# radio103.net
KiCad netlist of a schematic drawn in EAGLE
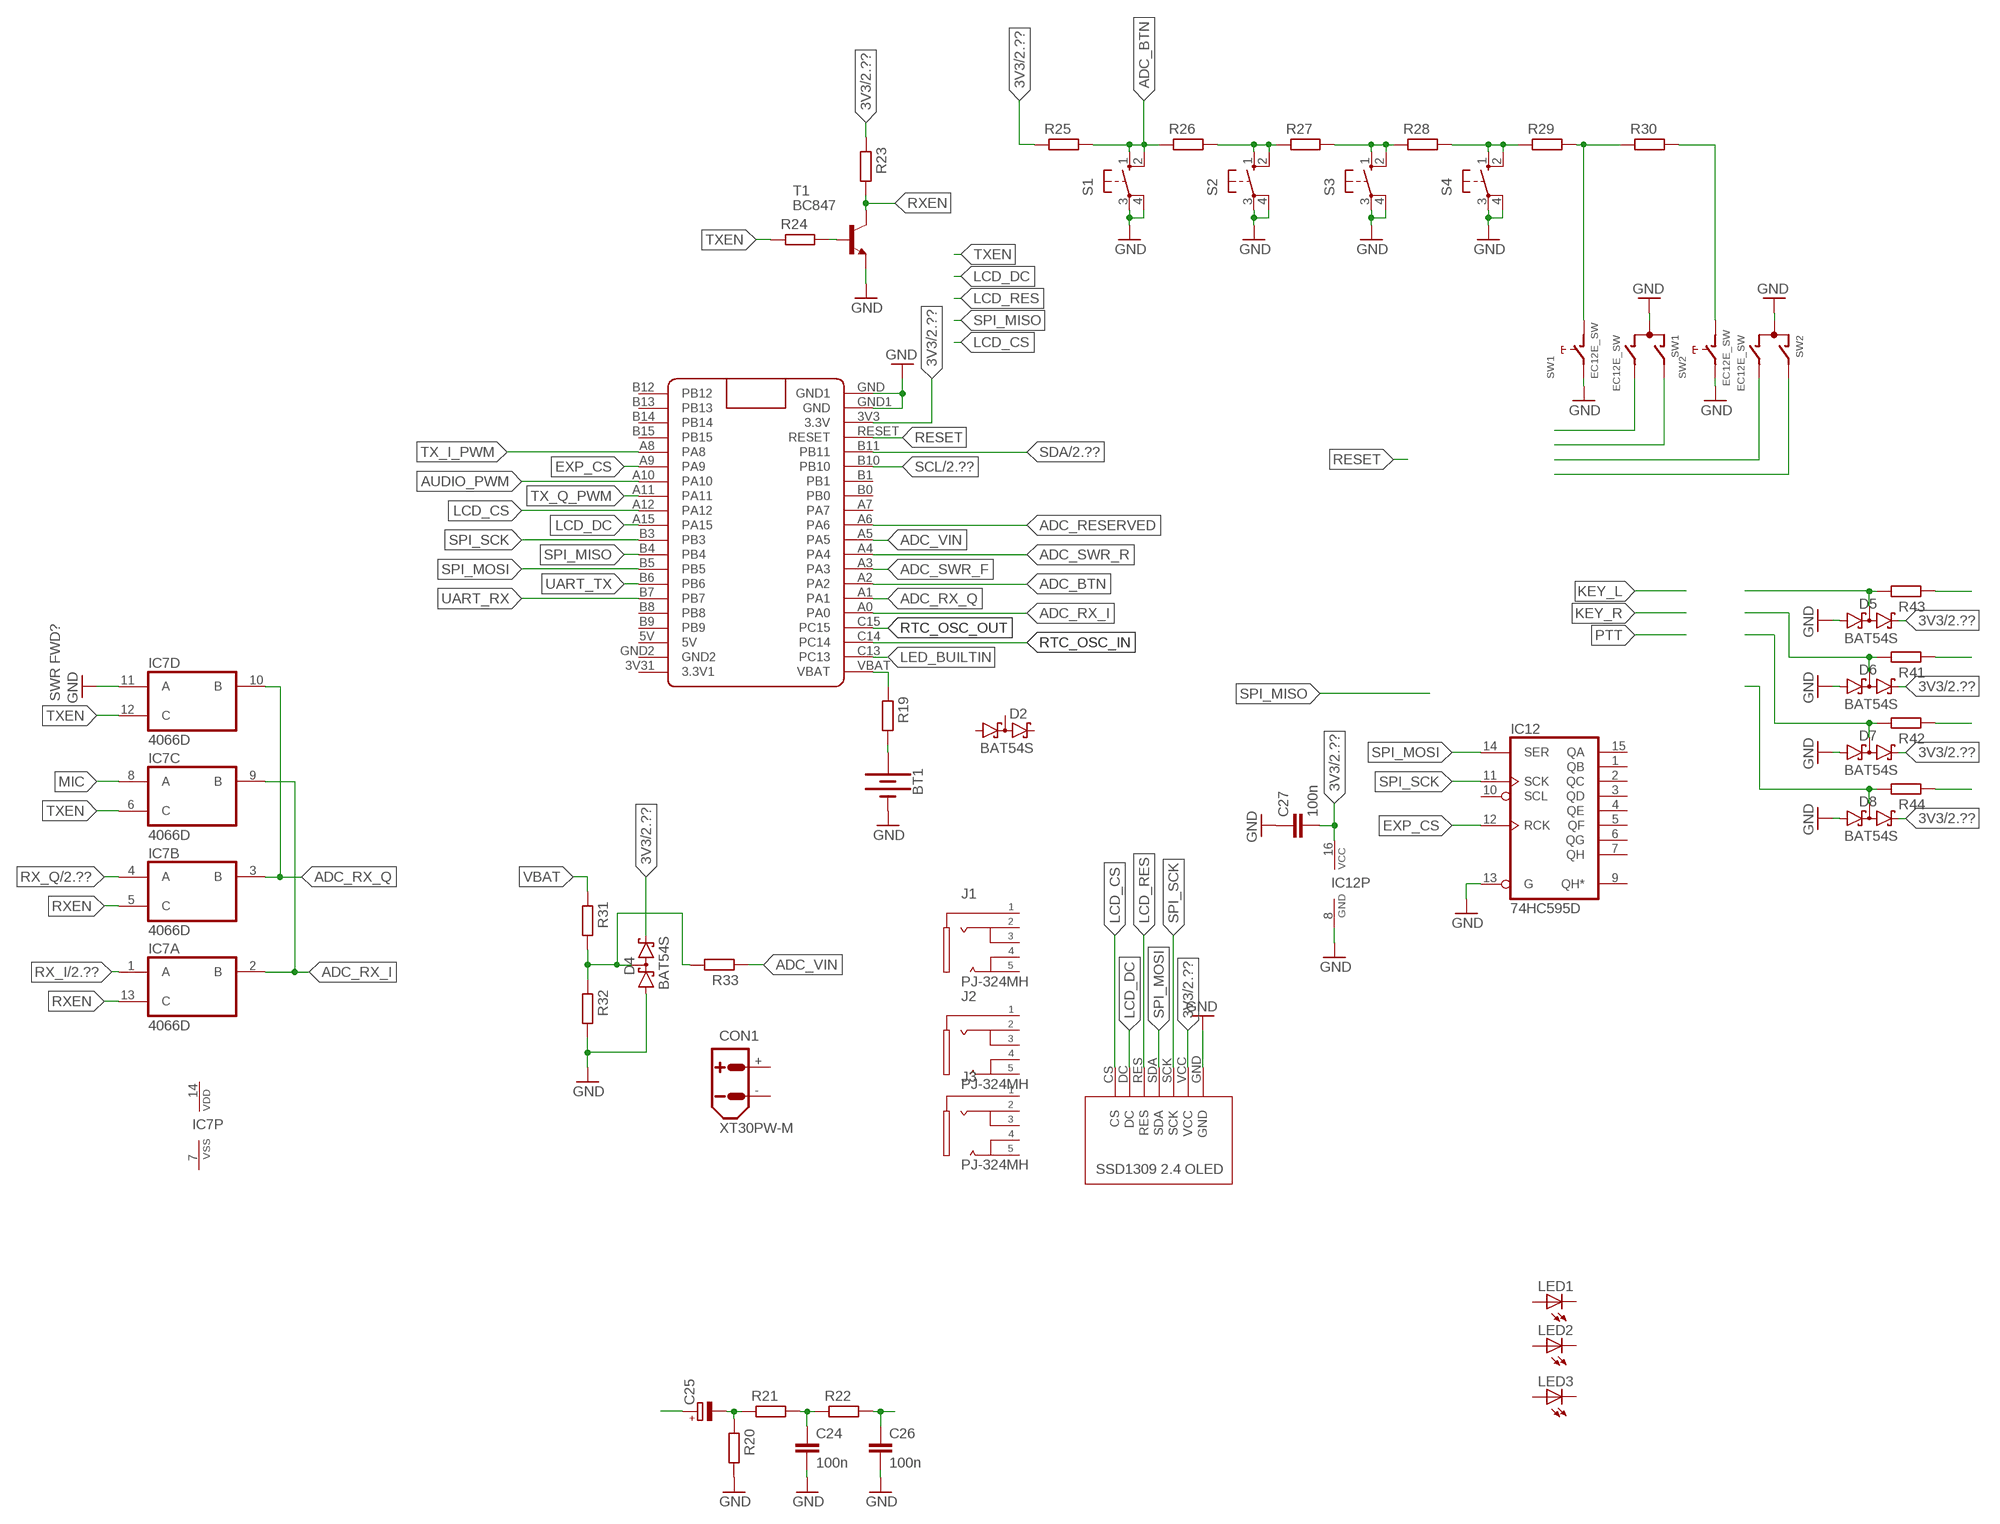
[diagram p0: schematic, sheet 1]
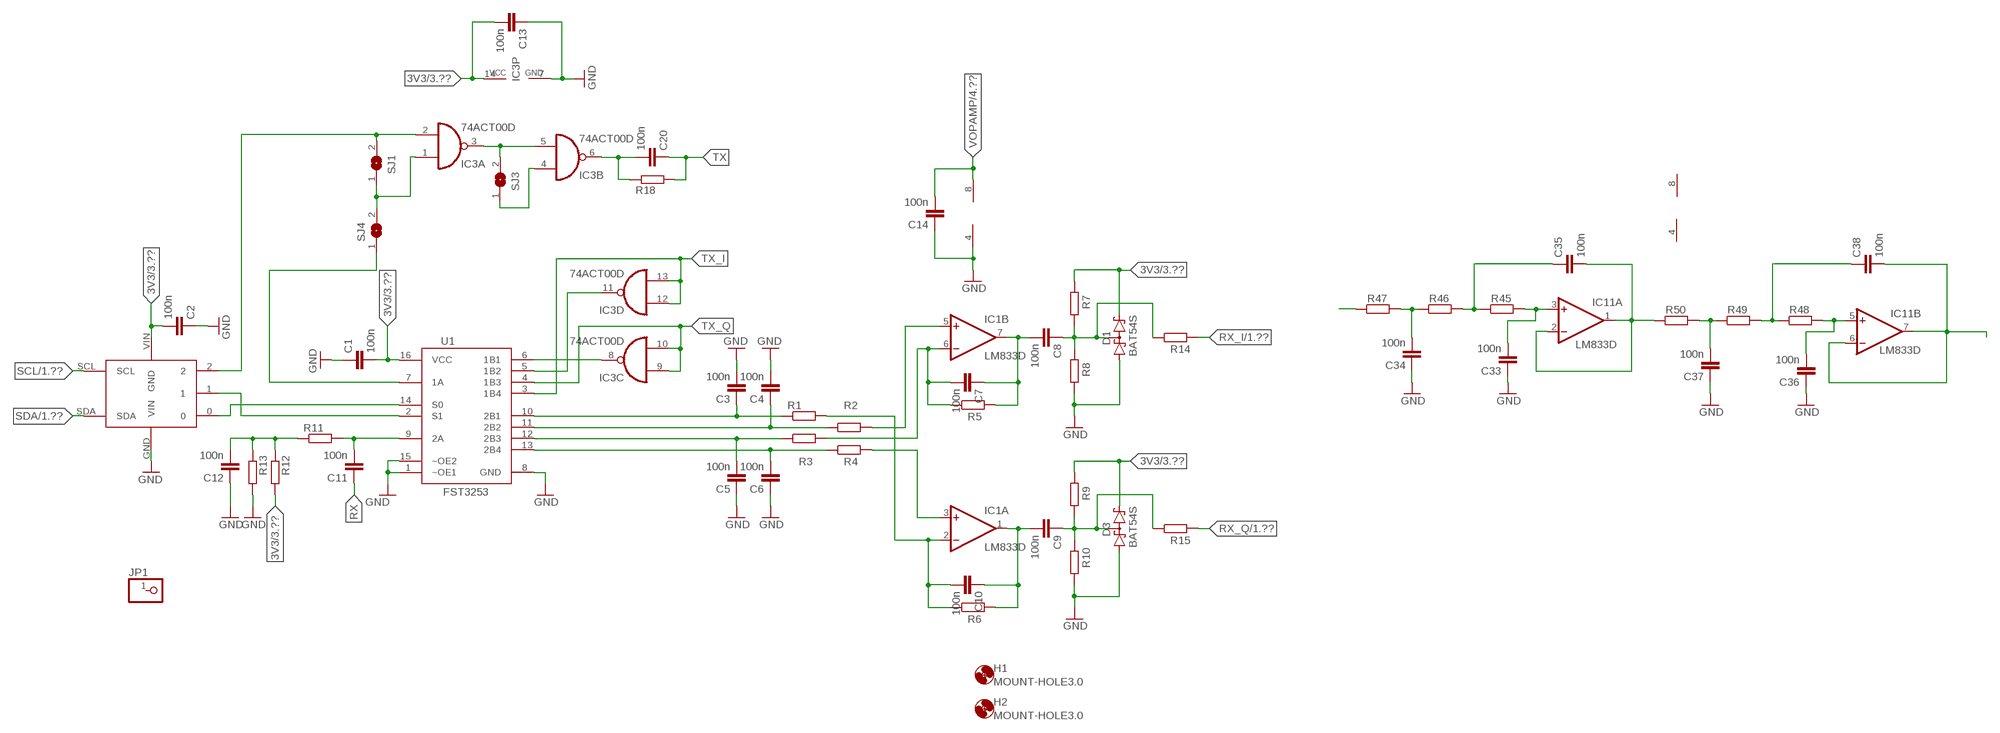
[diagram p1: schematic, sheet 2]
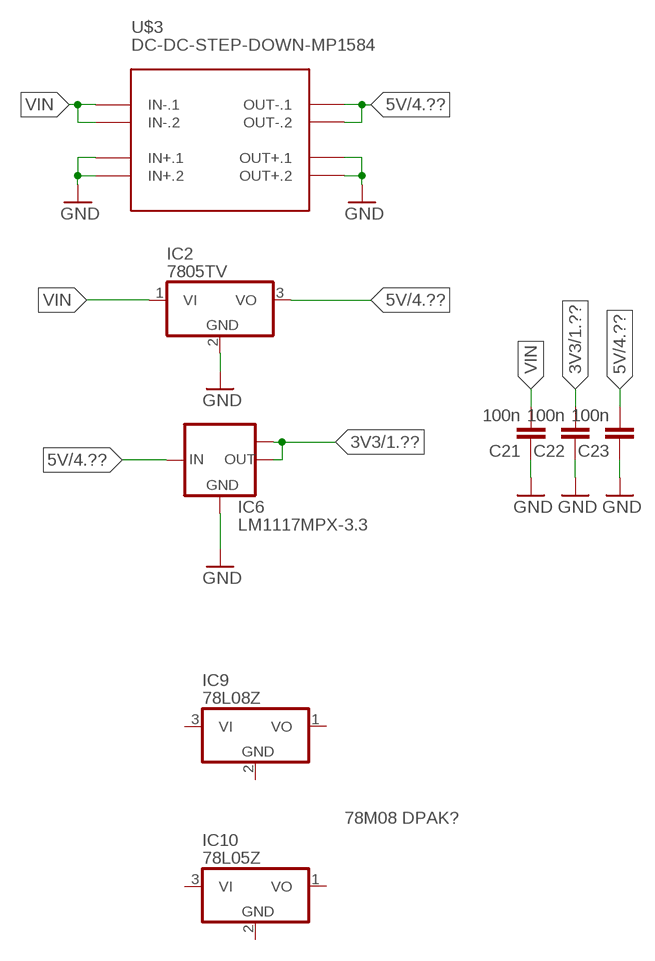
[diagram p2: schematic, sheet 3]
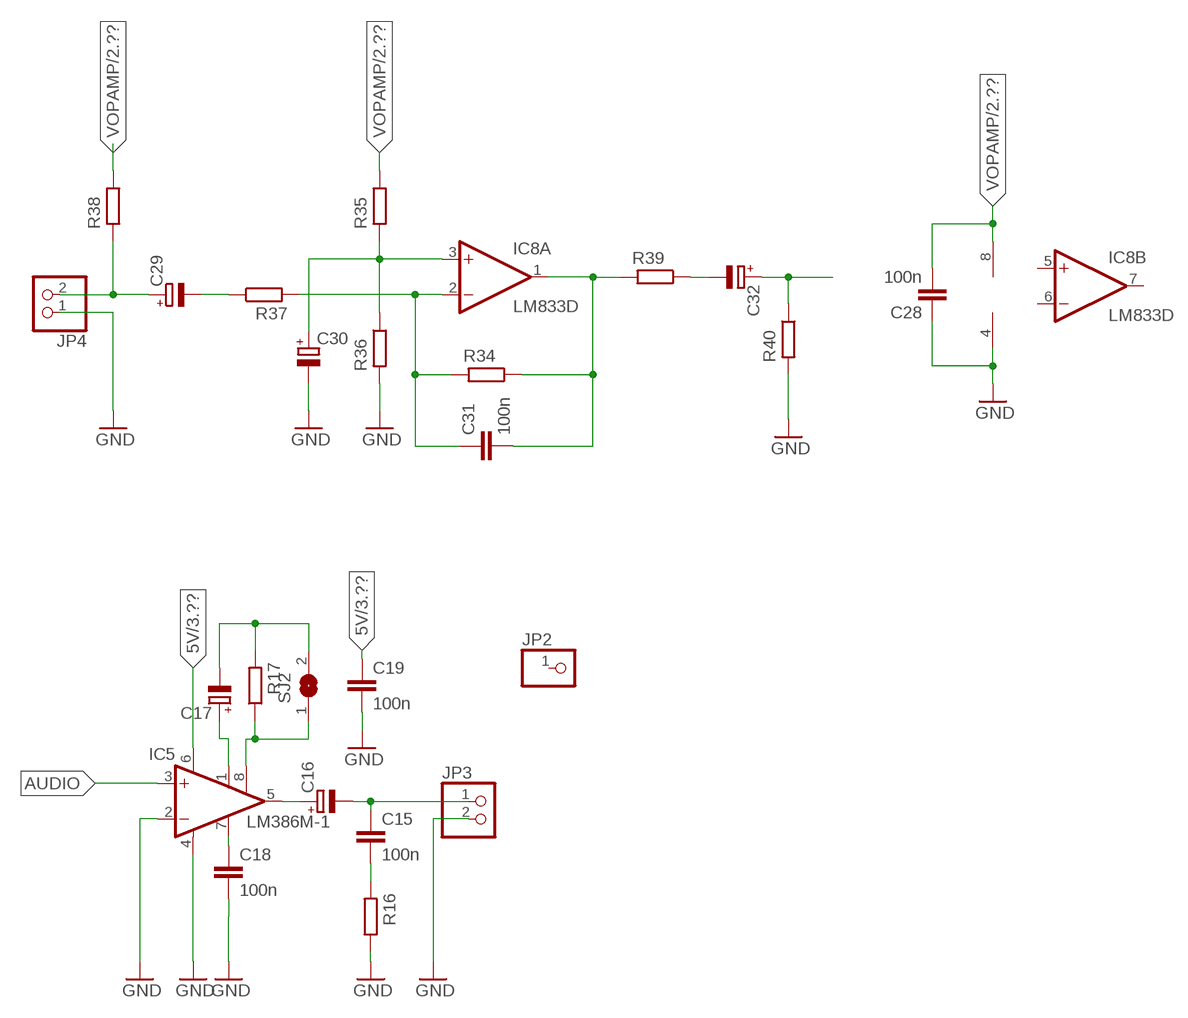
[diagram p3: schematic, sheet 4]

(export (version "E")
  (design (tool "Eeschema 10.0.6"))
  (components
    (comp (ref "C21")
      (value "100n")
      (footprint "eagle-import:C0805K")
      (libsource (lib "eagle-import") (part "C-EUC0805K"))
    )
    (comp (ref "C22")
      (value "100n")
      (footprint "eagle-import:C0805K")
      (libsource (lib "eagle-import") (part "C-EUC0805K"))
    )
    (comp (ref "C23")
      (value "100n")
      (footprint "eagle-import:C0805K")
      (libsource (lib "eagle-import") (part "C-EUC0805K"))
    )
    (comp (ref "IC2")
      (value "7805TV")
      (footprint "eagle-import:TO220V")
      (libsource (lib "eagle-import") (part "78TV05"))
    )
    (comp (ref "IC6")
      (value "LM1117MPX-3.3")
      (footprint "eagle-import:SOT223")
      (libsource (lib "eagle-import") (part "LM1117MPX-3.3"))
    )
    (comp (ref "IC9")
      (value "78L08Z")
      (footprint "eagle-import:TO92")
      (libsource (lib "eagle-import") (part "78ZL08"))
    )
    (comp (ref "IC10")
      (value "78L05Z")
      (footprint "eagle-import:TO92")
      (libsource (lib "eagle-import") (part "78ZL05"))
    )
    (comp (ref "U$3")
      (value "DC-DC-STEP-DOWN-MP1584")
      (footprint "eagle-import:DC-DC-STEP-DOWN-MP1584")
      (libsource (lib "eagle-import") (part "DC-DC-STEP-DOWN-MP1584"))
    )
    (comp (ref "C15")
      (value "100n")
      (footprint "eagle-import:C0805K")
      (libsource (lib "eagle-import") (part "C-EUC0805K"))
    )
    (comp (ref "C16")
      (value "CPOL-EUE2,5-6E")
      (footprint "eagle-import:E2,5-6E")
      (libsource (lib "eagle-import") (part "CPOL-EUE2,5-6E"))
    )
    (comp (ref "C17")
      (value "CPOL-EUE2,5-6E")
      (footprint "eagle-import:E2,5-6E")
      (libsource (lib "eagle-import") (part "CPOL-EUE2,5-6E"))
    )
    (comp (ref "C18")
      (value "100n")
      (footprint "eagle-import:C0805K")
      (libsource (lib "eagle-import") (part "C-EUC0805K"))
    )
    (comp (ref "C19")
      (value "100n")
      (footprint "eagle-import:C0805K")
      (libsource (lib "eagle-import") (part "C-EUC0805K"))
    )
    (comp (ref "C28")
      (value "100n")
      (footprint "eagle-import:C0805K")
      (libsource (lib "eagle-import") (part "C-EUC0805K"))
    )
    (comp (ref "C29")
      (value "CPOL-EUE2,5-6E")
      (footprint "eagle-import:E2,5-6E")
      (libsource (lib "eagle-import") (part "CPOL-EUE2,5-6E"))
    )
    (comp (ref "C30")
      (value "CPOL-EUE2,5-6E")
      (footprint "eagle-import:E2,5-6E")
      (libsource (lib "eagle-import") (part "CPOL-EUE2,5-6E"))
    )
    (comp (ref "C31")
      (value "100n")
      (footprint "eagle-import:C0805K")
      (libsource (lib "eagle-import") (part "C-EUC0805K"))
    )
    (comp (ref "C32")
      (value "CPOL-EUE2,5-6E")
      (footprint "eagle-import:E2,5-6E")
      (libsource (lib "eagle-import") (part "CPOL-EUE2,5-6E"))
    )
    (comp (ref "IC5")
      (value "LM386M-1")
      (footprint "eagle-import:SO08")
      (libsource (lib "eagle-import") (part "LM386?-M1"))
    )
    (comp (ref "IC8")
      (value "LM833D")
      (footprint "eagle-import:SO08")
      (libsource (lib "eagle-import") (part "LM833D"))
    )
    (comp (ref "JP2")
      (value "PINHD-1X1")
      (footprint "eagle-import:1X01")
      (libsource (lib "eagle-import") (part "PINHD-1X1"))
    )
    (comp (ref "JP3")
      (value "PINHD-1X2")
      (footprint "eagle-import:1X02")
      (libsource (lib "eagle-import") (part "PINHD-1X2"))
    )
    (comp (ref "JP4")
      (value "PINHD-1X2")
      (footprint "eagle-import:1X02")
      (libsource (lib "eagle-import") (part "PINHD-1X2"))
    )
    (comp (ref "R16")
      (value "R-EU_R0805")
      (footprint "eagle-import:R0805")
      (libsource (lib "eagle-import") (part "R-EU_R0805"))
    )
    (comp (ref "R17")
      (value "R-EU_R0805")
      (footprint "eagle-import:R0805")
      (libsource (lib "eagle-import") (part "R-EU_R0805"))
    )
    (comp (ref "R34")
      (value "R-EU_R0805")
      (footprint "eagle-import:R0805")
      (libsource (lib "eagle-import") (part "R-EU_R0805"))
    )
    (comp (ref "R35")
      (value "R-EU_R0805")
      (footprint "eagle-import:R0805")
      (libsource (lib "eagle-import") (part "R-EU_R0805"))
    )
    (comp (ref "R36")
      (value "R-EU_R0805")
      (footprint "eagle-import:R0805")
      (libsource (lib "eagle-import") (part "R-EU_R0805"))
    )
    (comp (ref "R37")
      (value "R-EU_R0805")
      (footprint "eagle-import:R0805")
      (libsource (lib "eagle-import") (part "R-EU_R0805"))
    )
    (comp (ref "R38")
      (value "R-EU_R0805")
      (footprint "eagle-import:R0805")
      (libsource (lib "eagle-import") (part "R-EU_R0805"))
    )
    (comp (ref "R39")
      (value "R-EU_R0805")
      (footprint "eagle-import:R0805")
      (libsource (lib "eagle-import") (part "R-EU_R0805"))
    )
    (comp (ref "R40")
      (value "R-EU_R0805")
      (footprint "eagle-import:R0805")
      (libsource (lib "eagle-import") (part "R-EU_R0805"))
    )
    (comp (ref "SJ2") (value "SJ") (footprint "eagle-import:SJ") (libsource (lib "eagle-import") (part "SJ")))
    (comp (ref "BT1")
      (value "BATTERY-12MM_SMD")
      (footprint "eagle-import:BATTCON_12MM")
      (libsource (lib "eagle-import") (part "BATTERY-12MM_SMD"))
    )
    (comp (ref "C24")
      (value "100n")
      (footprint "eagle-import:C0805K")
      (libsource (lib "eagle-import") (part "C-EUC0805K"))
    )
    (comp (ref "C25")
      (value "CPOL-EUE2,5-6E")
      (footprint "eagle-import:E2,5-6E")
      (libsource (lib "eagle-import") (part "CPOL-EUE2,5-6E"))
    )
    (comp (ref "C26")
      (value "100n")
      (footprint "eagle-import:C0805K")
      (libsource (lib "eagle-import") (part "C-EUC0805K"))
    )
    (comp (ref "C27")
      (value "100n")
      (footprint "eagle-import:C0805K")
      (libsource (lib "eagle-import") (part "C-EUC0805K"))
    )
    (comp (ref "CON1")
      (value "XT30PW-M")
      (footprint "eagle-import:XT30PW-M")
      (libsource (lib "eagle-import") (part "XT30PW-M"))
    )
    (comp (ref "D2")
      (value "BAT54S")
      (footprint "eagle-import:SOT23")
      (libsource (lib "eagle-import") (part "BAT54S"))
    )
    (comp (ref "D4")
      (value "BAT54S")
      (footprint "eagle-import:SOT23")
      (libsource (lib "eagle-import") (part "BAT54S"))
    )
    (comp (ref "D5")
      (value "BAT54S")
      (footprint "eagle-import:SOT23")
      (libsource (lib "eagle-import") (part "BAT54S"))
    )
    (comp (ref "D6")
      (value "BAT54S")
      (footprint "eagle-import:SOT23")
      (libsource (lib "eagle-import") (part "BAT54S"))
    )
    (comp (ref "D7")
      (value "BAT54S")
      (footprint "eagle-import:SOT23")
      (libsource (lib "eagle-import") (part "BAT54S"))
    )
    (comp (ref "D8")
      (value "BAT54S")
      (footprint "eagle-import:SOT23")
      (libsource (lib "eagle-import") (part "BAT54S"))
    )
    (comp (ref "IC7")
      (value "4066D")
      (footprint "eagle-import:SO14")
      (libsource (lib "eagle-import") (part "4066D"))
    )
    (comp (ref "IC12")
      (value "74HC595D")
      (footprint "eagle-import:SO16")
      (libsource (lib "eagle-import") (part "74595DHC"))
    )
    (comp (ref "J1")
      (value "PJ-324MH")
      (footprint "eagle-import:PJ-324MH")
      (libsource (lib "eagle-import") (part "PJ-324MH"))
    )
    (comp (ref "J2")
      (value "PJ-324MH")
      (footprint "eagle-import:PJ-324MH")
      (libsource (lib "eagle-import") (part "PJ-324MH"))
    )
    (comp (ref "J3")
      (value "PJ-324MH")
      (footprint "eagle-import:PJ-324MH")
      (libsource (lib "eagle-import") (part "PJ-324MH"))
    )
    (comp (ref "LED1")
      (value "OSYG1608")
      (footprint "eagle-import:C1608")
      (libsource (lib "eagle-import") (part "OSYG1608"))
    )
    (comp (ref "LED2")
      (value "OSYG1608")
      (footprint "eagle-import:C1608")
      (libsource (lib "eagle-import") (part "OSYG1608"))
    )
    (comp (ref "LED3")
      (value "OSYG1608")
      (footprint "eagle-import:C1608")
      (libsource (lib "eagle-import") (part "OSYG1608"))
    )
    (comp (ref "R19")
      (value "R-EU_R0805")
      (footprint "eagle-import:R0805")
      (libsource (lib "eagle-import") (part "R-EU_R0805"))
    )
    (comp (ref "R20")
      (value "R-EU_R0805")
      (footprint "eagle-import:R0805")
      (libsource (lib "eagle-import") (part "R-EU_R0805"))
    )
    (comp (ref "R21")
      (value "R-EU_R0805")
      (footprint "eagle-import:R0805")
      (libsource (lib "eagle-import") (part "R-EU_R0805"))
    )
    (comp (ref "R22")
      (value "R-EU_R0805")
      (footprint "eagle-import:R0805")
      (libsource (lib "eagle-import") (part "R-EU_R0805"))
    )
    (comp (ref "R23")
      (value "R-EU_R0805")
      (footprint "eagle-import:R0805")
      (libsource (lib "eagle-import") (part "R-EU_R0805"))
    )
    (comp (ref "R24")
      (value "R-EU_R0805")
      (footprint "eagle-import:R0805")
      (libsource (lib "eagle-import") (part "R-EU_R0805"))
    )
    (comp (ref "R25")
      (value "R-EU_R0805")
      (footprint "eagle-import:R0805")
      (libsource (lib "eagle-import") (part "R-EU_R0805"))
    )
    (comp (ref "R26")
      (value "R-EU_R0805")
      (footprint "eagle-import:R0805")
      (libsource (lib "eagle-import") (part "R-EU_R0805"))
    )
    (comp (ref "R27")
      (value "R-EU_R0805")
      (footprint "eagle-import:R0805")
      (libsource (lib "eagle-import") (part "R-EU_R0805"))
    )
    (comp (ref "R28")
      (value "R-EU_R0805")
      (footprint "eagle-import:R0805")
      (libsource (lib "eagle-import") (part "R-EU_R0805"))
    )
    (comp (ref "R29")
      (value "R-EU_R0805")
      (footprint "eagle-import:R0805")
      (libsource (lib "eagle-import") (part "R-EU_R0805"))
    )
    (comp (ref "R30")
      (value "R-EU_R0805")
      (footprint "eagle-import:R0805")
      (libsource (lib "eagle-import") (part "R-EU_R0805"))
    )
    (comp (ref "R31")
      (value "R-EU_R0805")
      (footprint "eagle-import:R0805")
      (libsource (lib "eagle-import") (part "R-EU_R0805"))
    )
    (comp (ref "R32")
      (value "R-EU_R0805")
      (footprint "eagle-import:R0805")
      (libsource (lib "eagle-import") (part "R-EU_R0805"))
    )
    (comp (ref "R33")
      (value "R-EU_R0805")
      (footprint "eagle-import:R0805")
      (libsource (lib "eagle-import") (part "R-EU_R0805"))
    )
    (comp (ref "R41")
      (value "R-EU_R0805")
      (footprint "eagle-import:R0805")
      (libsource (lib "eagle-import") (part "R-EU_R0805"))
    )
    (comp (ref "R42")
      (value "R-EU_R0805")
      (footprint "eagle-import:R0805")
      (libsource (lib "eagle-import") (part "R-EU_R0805"))
    )
    (comp (ref "R43")
      (value "R-EU_R0805")
      (footprint "eagle-import:R0805")
      (libsource (lib "eagle-import") (part "R-EU_R0805"))
    )
    (comp (ref "R44")
      (value "R-EU_R0805")
      (footprint "eagle-import:R0805")
      (libsource (lib "eagle-import") (part "R-EU_R0805"))
    )
    (comp (ref "S1")
      (value "10-XX")
      (footprint "eagle-import:B3F-10XX")
      (fields (field (name "MPN") "B3F-1000"))
      (libsource (lib "eagle-import") (part "10-XX"))
    )
    (comp (ref "S2")
      (value "10-XX")
      (footprint "eagle-import:B3F-10XX")
      (fields (field (name "MPN") "B3F-1000"))
      (libsource (lib "eagle-import") (part "10-XX"))
    )
    (comp (ref "S3")
      (value "10-XX")
      (footprint "eagle-import:B3F-10XX")
      (fields (field (name "MPN") "B3F-1000"))
      (libsource (lib "eagle-import") (part "10-XX"))
    )
    (comp (ref "S4")
      (value "10-XX")
      (footprint "eagle-import:B3F-10XX")
      (fields (field (name "MPN") "B3F-1000"))
      (libsource (lib "eagle-import") (part "10-XX"))
    )
    (comp (ref "SW1")
      (value "EC12E_SW")
      (footprint "eagle-import:ALPS_EC12E_SW")
      (fields (field (name "MPN") "EC12E2424407"))
      (libsource (lib "eagle-import") (part "EC12E_SW"))
    )
    (comp (ref "SW2")
      (value "EC12E_SW")
      (footprint "eagle-import:ALPS_EC12E_SW")
      (fields (field (name "MPN") "EC12E2424407"))
      (libsource (lib "eagle-import") (part "EC12E_SW"))
    )
    (comp (ref "T1")
      (value "BC847")
      (footprint "eagle-import:SOT23")
      (libsource (lib "eagle-import") (part "BC847"))
    )
    (comp (ref "U$1")
      (value "BLUE_PILL")
      (footprint "eagle-import:BLUE_PILL")
      (libsource (lib "eagle-import") (part "BLUE_PILL"))
    )
    (comp (ref "U$4")
      (value "SSD1309_2.4_OLED")
      (footprint "eagle-import:SSD1309_2.42_OLED")
      (libsource (lib "eagle-import") (part "SSD1309_2.4_OLED"))
    )
    (comp (ref "C1")
      (value "100n")
      (footprint "eagle-import:C0805K")
      (libsource (lib "eagle-import") (part "C-EUC0805K"))
    )
    (comp (ref "C2")
      (value "100n")
      (footprint "eagle-import:C0805K")
      (libsource (lib "eagle-import") (part "C-EUC0805K"))
    )
    (comp (ref "C3")
      (value "100n")
      (footprint "eagle-import:C0805K")
      (libsource (lib "eagle-import") (part "C-EUC0805K"))
    )
    (comp (ref "C4")
      (value "100n")
      (footprint "eagle-import:C0805K")
      (libsource (lib "eagle-import") (part "C-EUC0805K"))
    )
    (comp (ref "C5")
      (value "100n")
      (footprint "eagle-import:C0805K")
      (libsource (lib "eagle-import") (part "C-EUC0805K"))
    )
    (comp (ref "C6")
      (value "100n")
      (footprint "eagle-import:C0805K")
      (libsource (lib "eagle-import") (part "C-EUC0805K"))
    )
    (comp (ref "C7")
      (value "100n")
      (footprint "eagle-import:C0805K")
      (libsource (lib "eagle-import") (part "C-EUC0805K"))
    )
    (comp (ref "C8")
      (value "100n")
      (footprint "eagle-import:C0805K")
      (libsource (lib "eagle-import") (part "C-EUC0805K"))
    )
    (comp (ref "C9")
      (value "100n")
      (footprint "eagle-import:C0805K")
      (libsource (lib "eagle-import") (part "C-EUC0805K"))
    )
    (comp (ref "C10")
      (value "100n")
      (footprint "eagle-import:C0805K")
      (libsource (lib "eagle-import") (part "C-EUC0805K"))
    )
    (comp (ref "C11")
      (value "100n")
      (footprint "eagle-import:C0805K")
      (libsource (lib "eagle-import") (part "C-EUC0805K"))
    )
    (comp (ref "C12")
      (value "100n")
      (footprint "eagle-import:C0805K")
      (libsource (lib "eagle-import") (part "C-EUC0805K"))
    )
    (comp (ref "C13")
      (value "100n")
      (footprint "eagle-import:C0805K")
      (libsource (lib "eagle-import") (part "C-EUC0805K"))
    )
    (comp (ref "C14")
      (value "100n")
      (footprint "eagle-import:C0805K")
      (libsource (lib "eagle-import") (part "C-EUC0805K"))
    )
    (comp (ref "C20")
      (value "100n")
      (footprint "eagle-import:C0805K")
      (libsource (lib "eagle-import") (part "C-EUC0805K"))
    )
    (comp (ref "C33")
      (value "100n")
      (footprint "eagle-import:C0805K")
      (libsource (lib "eagle-import") (part "C-EUC0805K"))
    )
    (comp (ref "C34")
      (value "100n")
      (footprint "eagle-import:C0805K")
      (libsource (lib "eagle-import") (part "C-EUC0805K"))
    )
    (comp (ref "C35")
      (value "100n")
      (footprint "eagle-import:C0805K")
      (libsource (lib "eagle-import") (part "C-EUC0805K"))
    )
    (comp (ref "C36")
      (value "100n")
      (footprint "eagle-import:C0805K")
      (libsource (lib "eagle-import") (part "C-EUC0805K"))
    )
    (comp (ref "C37")
      (value "100n")
      (footprint "eagle-import:C0805K")
      (libsource (lib "eagle-import") (part "C-EUC0805K"))
    )
    (comp (ref "C38")
      (value "100n")
      (footprint "eagle-import:C0805K")
      (libsource (lib "eagle-import") (part "C-EUC0805K"))
    )
    (comp (ref "D1")
      (value "BAT54S")
      (footprint "eagle-import:SOT23")
      (libsource (lib "eagle-import") (part "BAT54S"))
    )
    (comp (ref "D3")
      (value "BAT54S")
      (footprint "eagle-import:SOT23")
      (libsource (lib "eagle-import") (part "BAT54S"))
    )
    (comp (ref "H1")
      (value "MOUNT-HOLE3.0")
      (footprint "eagle-import:3,0")
      (libsource (lib "eagle-import") (part "MOUNT-HOLE3.0"))
    )
    (comp (ref "H2")
      (value "MOUNT-HOLE3.0")
      (footprint "eagle-import:3,0")
      (libsource (lib "eagle-import") (part "MOUNT-HOLE3.0"))
    )
    (comp (ref "IC1")
      (value "LM833D")
      (footprint "eagle-import:SO08")
      (libsource (lib "eagle-import") (part "LM833D"))
    )
    (comp (ref "IC3")
      (value "74ACT00D")
      (footprint "eagle-import:SO14")
      (libsource (lib "eagle-import") (part "7400DACT"))
    )
    (comp (ref "IC11")
      (value "LM833D")
      (footprint "eagle-import:SO08")
      (libsource (lib "eagle-import") (part "LM833D"))
    )
    (comp (ref "JP1")
      (value "PINHD-1X1")
      (footprint "eagle-import:1X01")
      (libsource (lib "eagle-import") (part "PINHD-1X1"))
    )
    (comp (ref "R1")
      (value "R-EU_R0805")
      (footprint "eagle-import:R0805")
      (libsource (lib "eagle-import") (part "R-EU_R0805"))
    )
    (comp (ref "R2")
      (value "R-EU_R0805")
      (footprint "eagle-import:R0805")
      (libsource (lib "eagle-import") (part "R-EU_R0805"))
    )
    (comp (ref "R3")
      (value "R-EU_R0805")
      (footprint "eagle-import:R0805")
      (libsource (lib "eagle-import") (part "R-EU_R0805"))
    )
    (comp (ref "R4")
      (value "R-EU_R0805")
      (footprint "eagle-import:R0805")
      (libsource (lib "eagle-import") (part "R-EU_R0805"))
    )
    (comp (ref "R5")
      (value "R-EU_R0805")
      (footprint "eagle-import:R0805")
      (libsource (lib "eagle-import") (part "R-EU_R0805"))
    )
    (comp (ref "R6")
      (value "R-EU_R0805")
      (footprint "eagle-import:R0805")
      (libsource (lib "eagle-import") (part "R-EU_R0805"))
    )
    (comp (ref "R7")
      (value "R-EU_R0805")
      (footprint "eagle-import:R0805")
      (libsource (lib "eagle-import") (part "R-EU_R0805"))
    )
    (comp (ref "R8")
      (value "R-EU_R0805")
      (footprint "eagle-import:R0805")
      (libsource (lib "eagle-import") (part "R-EU_R0805"))
    )
    (comp (ref "R9")
      (value "R-EU_R0805")
      (footprint "eagle-import:R0805")
      (libsource (lib "eagle-import") (part "R-EU_R0805"))
    )
    (comp (ref "R10")
      (value "R-EU_R0805")
      (footprint "eagle-import:R0805")
      (libsource (lib "eagle-import") (part "R-EU_R0805"))
    )
    (comp (ref "R11")
      (value "R-EU_R0805")
      (footprint "eagle-import:R0805")
      (libsource (lib "eagle-import") (part "R-EU_R0805"))
    )
    (comp (ref "R12")
      (value "R-EU_R0805")
      (footprint "eagle-import:R0805")
      (libsource (lib "eagle-import") (part "R-EU_R0805"))
    )
    (comp (ref "R13")
      (value "R-EU_R0805")
      (footprint "eagle-import:R0805")
      (libsource (lib "eagle-import") (part "R-EU_R0805"))
    )
    (comp (ref "R14")
      (value "R-EU_R0805")
      (footprint "eagle-import:R0805")
      (libsource (lib "eagle-import") (part "R-EU_R0805"))
    )
    (comp (ref "R15")
      (value "R-EU_R0805")
      (footprint "eagle-import:R0805")
      (libsource (lib "eagle-import") (part "R-EU_R0805"))
    )
    (comp (ref "R18")
      (value "R-EU_R0805")
      (footprint "eagle-import:R0805")
      (libsource (lib "eagle-import") (part "R-EU_R0805"))
    )
    (comp (ref "R45")
      (value "R-EU_R0805")
      (footprint "eagle-import:R0805")
      (libsource (lib "eagle-import") (part "R-EU_R0805"))
    )
    (comp (ref "R46")
      (value "R-EU_R0805")
      (footprint "eagle-import:R0805")
      (libsource (lib "eagle-import") (part "R-EU_R0805"))
    )
    (comp (ref "R47")
      (value "R-EU_R0805")
      (footprint "eagle-import:R0805")
      (libsource (lib "eagle-import") (part "R-EU_R0805"))
    )
    (comp (ref "R48")
      (value "R-EU_R0805")
      (footprint "eagle-import:R0805")
      (libsource (lib "eagle-import") (part "R-EU_R0805"))
    )
    (comp (ref "R49")
      (value "R-EU_R0805")
      (footprint "eagle-import:R0805")
      (libsource (lib "eagle-import") (part "R-EU_R0805"))
    )
    (comp (ref "R50")
      (value "R-EU_R0805")
      (footprint "eagle-import:R0805")
      (libsource (lib "eagle-import") (part "R-EU_R0805"))
    )
    (comp (ref "SJ1") (value "SJ") (footprint "eagle-import:SJ") (libsource (lib "eagle-import") (part "SJ")))
    (comp (ref "SJ3") (value "SJ") (footprint "eagle-import:SJ") (libsource (lib "eagle-import") (part "SJ")))
    (comp (ref "SJ4") (value "SJ") (footprint "eagle-import:SJ") (libsource (lib "eagle-import") (part "SJ")))
    (comp (ref "U$2")
      (value "CJMCU-5351")
      (footprint "eagle-import:CJMCU-5351")
      (libsource (lib "eagle-import") (part "CJMCU-5351"))
    )
    (comp (ref "U1")
      (value "FST3253")
      (footprint "eagle-import:TSSOP16L")
      (libsource (lib "eagle-import") (part "FST3253"))
    )
  )
  (nets
    (net (code "1") (name "+") (class "Default")
      (node (ref "CON1") (pin "+") (pinfunction "+_+") (pintype "power_in"))
    )
    (net (code "2") (name "-") (class "Default")
      (node (ref "CON1") (pin "-") (pinfunction "-_-") (pintype "power_in"))
    )
    (net (code "3") (name "3V3") (class "Default")
      (node (ref "C1") (pin "2") (pinfunction "2_2") (pintype "passive"))
      (node (ref "C13") (pin "2") (pinfunction "2_2") (pintype "passive"))
      (node (ref "C2") (pin "2") (pinfunction "2_2") (pintype "passive"))
      (node (ref "C22") (pin "2") (pinfunction "2_2") (pintype "passive"))
      (node (ref "C27") (pin "2") (pinfunction "2_2") (pintype "passive"))
      (node (ref "D1") (pin "2") (pinfunction "C2_2") (pintype "passive"))
      (node (ref "D3") (pin "2") (pinfunction "C2_2") (pintype "passive"))
      (node (ref "D4") (pin "2") (pinfunction "C2_2") (pintype "passive"))
      (node (ref "D5") (pin "2") (pinfunction "C2_2") (pintype "passive"))
      (node (ref "D6") (pin "2") (pinfunction "C2_2") (pintype "passive"))
      (node (ref "D7") (pin "2") (pinfunction "C2_2") (pintype "passive"))
      (node (ref "D8") (pin "2") (pinfunction "C2_2") (pintype "passive"))
      (node (ref "IC12") (pin "16") (pinfunction "VCC_16") (pintype "power_in"))
      (node (ref "IC3") (pin "14") (pinfunction "VCC_14") (pintype "power_in"))
      (node (ref "IC6") (pin "2") (pinfunction "OUT_2") (pintype "passive"))
      (node (ref "IC6") (pin "TAB") (pinfunction "OUT1_TAB") (pintype "passive"))
      (node (ref "R12") (pin "2") (pinfunction "2_2") (pintype "passive"))
      (node (ref "R23") (pin "2") (pinfunction "2_2") (pintype "passive"))
      (node (ref "R25") (pin "2") (pinfunction "2_2") (pintype "passive"))
      (node (ref "R7") (pin "2") (pinfunction "2_2") (pintype "passive"))
      (node (ref "R9") (pin "2") (pinfunction "2_2") (pintype "passive"))
      (node (ref "U$1") (pin "3V3") (pinfunction "3.3V_3V3") (pintype "bidirectional"))
      (node (ref "U$2") (pin "VIN") (pinfunction "GND_VIN") (pintype "bidirectional"))
      (node (ref "U$4") (pin "VCC") (pinfunction "VCC_VCC") (pintype "bidirectional"))
      (node (ref "U1") (pin "16") (pinfunction "VCC_16") (pintype "bidirectional"))
    )
    (net (code "4") (name "5V") (class "Default")
      (node (ref "C19") (pin "1") (pinfunction "1_1") (pintype "passive"))
      (node (ref "C23") (pin "2") (pinfunction "2_2") (pintype "passive"))
      (node (ref "IC2") (pin "3") (pinfunction "VO_3") (pintype "passive"))
      (node (ref "IC5") (pin "6") (pinfunction "VS_6") (pintype "power_in"))
      (node (ref "IC6") (pin "3") (pinfunction "IN_3") (pintype "input"))
      (node (ref "U$3") (pin "OUT-.1") (pinfunction "OUT-.1_OUT-.1") (pintype "bidirectional"))
      (node (ref "U$3") (pin "OUT-.2") (pinfunction "OUT-.2_OUT-.2") (pintype "bidirectional"))
    )
    (net (code "5") (name "ADC_BTN") (class "Default")
      (node (ref "R25") (pin "1") (pinfunction "1_1") (pintype "passive"))
      (node (ref "R26") (pin "2") (pinfunction "2_2") (pintype "passive"))
      (node (ref "S1") (pin "1") (pinfunction "S_1") (pintype "passive"))
      (node (ref "S1") (pin "2") (pinfunction "S1_2") (pintype "passive"))
      (node (ref "U$1") (pin "A2") (pinfunction "PA2_A2") (pintype "bidirectional"))
    )
    (net (code "6") (name "ADC_RESERVED") (class "Default")
      (node (ref "U$1") (pin "A6") (pinfunction "PA6_A6") (pintype "bidirectional"))
    )
    (net (code "7") (name "ADC_RX_I") (class "Default")
      (node (ref "IC7") (pin "2") (pinfunction "B_2") (pintype "tri_state"))
      (node (ref "IC7") (pin "9") (pinfunction "B_9") (pintype "tri_state"))
      (node (ref "U$1") (pin "A0") (pinfunction "PA0_A0") (pintype "bidirectional"))
    )
    (net (code "8") (name "ADC_RX_Q") (class "Default")
      (node (ref "IC7") (pin "10") (pinfunction "B_10") (pintype "tri_state"))
      (node (ref "IC7") (pin "3") (pinfunction "B_3") (pintype "tri_state"))
      (node (ref "U$1") (pin "A1") (pinfunction "PA1_A1") (pintype "bidirectional"))
    )
    (net (code "9") (name "ADC_SWR_F") (class "Default")
      (node (ref "U$1") (pin "A3") (pinfunction "PA3_A3") (pintype "bidirectional"))
    )
    (net (code "10") (name "ADC_SWR_R") (class "Default")
      (node (ref "U$1") (pin "A4") (pinfunction "PA4_A4") (pintype "bidirectional"))
    )
    (net (code "11") (name "ADC_VIN") (class "Default")
      (node (ref "R33") (pin "2") (pinfunction "2_2") (pintype "passive"))
      (node (ref "U$1") (pin "A5") (pinfunction "PA5_A5") (pintype "bidirectional"))
    )
    (net (code "12") (name "AUDIO") (class "Default")
      (node (ref "IC5") (pin "3") (pinfunction "+IN_3") (pintype "input"))
    )
    (net (code "13") (name "AUDIO_PWM") (class "Default")
      (node (ref "U$1") (pin "A10") (pinfunction "PA10_A10") (pintype "bidirectional"))
    )
    (net (code "14") (name "EXP_CS") (class "Default")
      (node (ref "IC12") (pin "12") (pinfunction "RCK_12") (pintype "input"))
      (node (ref "U$1") (pin "A9") (pinfunction "PA9_A9") (pintype "bidirectional"))
    )
    (net (code "15") (name "GND") (class "Default")
      (node (ref "BT1") (pin "GND") (pinfunction "-_GND") (pintype "power_in"))
      (node (ref "C1") (pin "1") (pinfunction "1_1") (pintype "passive"))
      (node (ref "C12") (pin "1") (pinfunction "1_1") (pintype "passive"))
      (node (ref "C13") (pin "1") (pinfunction "1_1") (pintype "passive"))
      (node (ref "C14") (pin "1") (pinfunction "1_1") (pintype "passive"))
      (node (ref "C18") (pin "2") (pinfunction "2_2") (pintype "passive"))
      (node (ref "C19") (pin "2") (pinfunction "2_2") (pintype "passive"))
      (node (ref "C2") (pin "1") (pinfunction "1_1") (pintype "passive"))
      (node (ref "C21") (pin "1") (pinfunction "1_1") (pintype "passive"))
      (node (ref "C22") (pin "1") (pinfunction "1_1") (pintype "passive"))
      (node (ref "C23") (pin "1") (pinfunction "1_1") (pintype "passive"))
      (node (ref "C24") (pin "2") (pinfunction "2_2") (pintype "passive"))
      (node (ref "C26") (pin "2") (pinfunction "2_2") (pintype "passive"))
      (node (ref "C27") (pin "1") (pinfunction "1_1") (pintype "passive"))
      (node (ref "C28") (pin "1") (pinfunction "1_1") (pintype "passive"))
      (node (ref "C3") (pin "2") (pinfunction "2_2") (pintype "passive"))
      (node (ref "C30") (pin "-") (pinfunction "-_-") (pintype "passive"))
      (node (ref "C33") (pin "1") (pinfunction "1_1") (pintype "passive"))
      (node (ref "C34") (pin "1") (pinfunction "1_1") (pintype "passive"))
      (node (ref "C36") (pin "1") (pinfunction "1_1") (pintype "passive"))
      (node (ref "C37") (pin "1") (pinfunction "1_1") (pintype "passive"))
      (node (ref "C4") (pin "2") (pinfunction "2_2") (pintype "passive"))
      (node (ref "C5") (pin "1") (pinfunction "1_1") (pintype "passive"))
      (node (ref "C6") (pin "1") (pinfunction "1_1") (pintype "passive"))
      (node (ref "D1") (pin "1") (pinfunction "A1_1") (pintype "passive"))
      (node (ref "D3") (pin "1") (pinfunction "A1_1") (pintype "passive"))
      (node (ref "D4") (pin "1") (pinfunction "A1_1") (pintype "passive"))
      (node (ref "D5") (pin "1") (pinfunction "A1_1") (pintype "passive"))
      (node (ref "D6") (pin "1") (pinfunction "A1_1") (pintype "passive"))
      (node (ref "D7") (pin "1") (pinfunction "A1_1") (pintype "passive"))
      (node (ref "D8") (pin "1") (pinfunction "A1_1") (pintype "passive"))
      (node (ref "IC1") (pin "4") (pinfunction "V-_4") (pintype "power_in"))
      (node (ref "IC12") (pin "13") (pinfunction "G_13") (pintype "input"))
      (node (ref "IC12") (pin "8") (pinfunction "GND_8") (pintype "power_in"))
      (node (ref "IC2") (pin "2") (pinfunction "GND_2") (pintype "passive"))
      (node (ref "IC3") (pin "7") (pinfunction "GND_7") (pintype "power_in"))
      (node (ref "IC5") (pin "2") (pinfunction "-IN_2") (pintype "input"))
      (node (ref "IC5") (pin "4") (pinfunction "GND_4") (pintype "power_in"))
      (node (ref "IC6") (pin "1") (pinfunction "GND_1") (pintype "input"))
      (node (ref "IC7") (pin "11") (pinfunction "A_11") (pintype "tri_state"))
      (node (ref "IC8") (pin "4") (pinfunction "V-_4") (pintype "power_in"))
      (node (ref "JP3") (pin "2") (pinfunction "2_2") (pintype "passive"))
      (node (ref "JP4") (pin "1") (pinfunction "1_1") (pintype "passive"))
      (node (ref "R10") (pin "1") (pinfunction "1_1") (pintype "passive"))
      (node (ref "R13") (pin "2") (pinfunction "2_2") (pintype "passive"))
      (node (ref "R16") (pin "1") (pinfunction "1_1") (pintype "passive"))
      (node (ref "R20") (pin "1") (pinfunction "1_1") (pintype "passive"))
      (node (ref "R32") (pin "1") (pinfunction "1_1") (pintype "passive"))
      (node (ref "R36") (pin "2") (pinfunction "2_2") (pintype "passive"))
      (node (ref "R40") (pin "2") (pinfunction "2_2") (pintype "passive"))
      (node (ref "R8") (pin "1") (pinfunction "1_1") (pintype "passive"))
      (node (ref "S1") (pin "3") (pinfunction "P_3") (pintype "passive"))
      (node (ref "S1") (pin "4") (pinfunction "P1_4") (pintype "passive"))
      (node (ref "S2") (pin "3") (pinfunction "P_3") (pintype "passive"))
      (node (ref "S2") (pin "4") (pinfunction "P1_4") (pintype "passive"))
      (node (ref "S3") (pin "3") (pinfunction "P_3") (pintype "passive"))
      (node (ref "S3") (pin "4") (pinfunction "P1_4") (pintype "passive"))
      (node (ref "S4") (pin "3") (pinfunction "P_3") (pintype "passive"))
      (node (ref "S4") (pin "4") (pinfunction "P1_4") (pintype "passive"))
      (node (ref "SW1") (pin "C") (pinfunction "C_C") (pintype "passive"))
      (node (ref "SW1") (pin "E") (pinfunction "2_E") (pintype "passive"))
      (node (ref "SW2") (pin "C") (pinfunction "C_C") (pintype "passive"))
      (node (ref "SW2") (pin "E") (pinfunction "2_E") (pintype "passive"))
      (node (ref "T1") (pin "2") (pinfunction "E_2") (pintype "passive"))
      (node (ref "U$1") (pin "GND") (pinfunction "GND1_GND") (pintype "power_in"))
      (node (ref "U$1") (pin "GND1") (pinfunction "GND_GND1") (pintype "bidirectional"))
      (node (ref "U$2") (pin "GND") (pinfunction "VIN_GND") (pintype "bidirectional"))
      (node (ref "U$3") (pin "IN+.1") (pinfunction "IN+.1_IN+.1") (pintype "bidirectional"))
      (node (ref "U$3") (pin "IN+.2") (pinfunction "IN+.2_IN+.2") (pintype "bidirectional"))
      (node (ref "U$3") (pin "OUT+.1") (pinfunction "OUT+.1_OUT+.1") (pintype "bidirectional"))
      (node (ref "U$3") (pin "OUT+.2") (pinfunction "OUT+.2_OUT+.2") (pintype "bidirectional"))
      (node (ref "U$4") (pin "GND") (pinfunction "GND_GND") (pintype "bidirectional"))
      (node (ref "U1") (pin "1") (pinfunction "~{OE1}_1") (pintype "bidirectional"))
      (node (ref "U1") (pin "15") (pinfunction "~{OE2}_15") (pintype "bidirectional"))
      (node (ref "U1") (pin "8") (pinfunction "GND_8") (pintype "bidirectional"))
    )
    (net (code "18") (name "LCD_CS") (class "Default")
      (node (ref "U$1") (pin "A12") (pinfunction "PA12_A12") (pintype "bidirectional"))
      (node (ref "U$4") (pin "CS") (pinfunction "CS_CS") (pintype "bidirectional"))
    )
    (net (code "19") (name "LCD_DC") (class "Default")
      (node (ref "U$1") (pin "A15") (pinfunction "PA15_A15") (pintype "bidirectional"))
      (node (ref "U$4") (pin "DC") (pinfunction "DC_DC") (pintype "bidirectional"))
    )
    (net (code "20") (name "LCD_RES") (class "Default")
      (node (ref "U$4") (pin "RES") (pinfunction "RES_RES") (pintype "bidirectional"))
    )
    (net (code "21") (name "LED_BUILTIN") (class "Default")
      (node (ref "U$1") (pin "C13") (pinfunction "PC13_C13") (pintype "bidirectional"))
    )
    (net (code "22") (name "MIC") (class "Default")
      (node (ref "IC7") (pin "8") (pinfunction "A_8") (pintype "tri_state"))
    )
    (net (code "23") (name "Net-(BT1-+)") (class "Default")
      (node (ref "BT1") (pin "PWR@1") (pinfunction "+_PWR@1") (pintype "power_in"))
      (node (ref "R19") (pin "1") (pinfunction "1_1") (pintype "passive"))
    )
    (net (code "24") (name "Net-(C12-Pad2)") (class "Default")
      (node (ref "C12") (pin "2") (pinfunction "2_2") (pintype "passive"))
      (node (ref "R11") (pin "1") (pinfunction "1_1") (pintype "passive"))
      (node (ref "R12") (pin "1") (pinfunction "1_1") (pintype "passive"))
      (node (ref "R13") (pin "1") (pinfunction "1_1") (pintype "passive"))
    )
    (net (code "25") (name "Net-(C15-Pad1)") (class "Default")
      (node (ref "C15") (pin "1") (pinfunction "1_1") (pintype "passive"))
      (node (ref "C16") (pin "-") (pinfunction "-_-") (pintype "passive"))
      (node (ref "JP3") (pin "1") (pinfunction "1_1") (pintype "passive"))
    )
    (net (code "26") (name "Net-(C15-Pad2)") (class "Default")
      (node (ref "C15") (pin "2") (pinfunction "2_2") (pintype "passive"))
      (node (ref "R16") (pin "2") (pinfunction "2_2") (pintype "passive"))
    )
    (net (code "27") (name "Net-(C17-Pad+)") (class "Default")
      (node (ref "C17") (pin "+") (pinfunction "+_+") (pintype "passive"))
      (node (ref "IC5") (pin "1") (pinfunction "GAIN_1") (pintype "passive"))
    )
    (net (code "28") (name "Net-(C17-Pad-)") (class "Default")
      (node (ref "C17") (pin "-") (pinfunction "-_-") (pintype "passive"))
      (node (ref "R17") (pin "2") (pinfunction "2_2") (pintype "passive"))
      (node (ref "SJ2") (pin "2") (pinfunction "2_2") (pintype "passive"))
    )
    (net (code "29") (name "Net-(C24-Pad1)") (class "Default")
      (node (ref "C24") (pin "1") (pinfunction "1_1") (pintype "passive"))
      (node (ref "R21") (pin "1") (pinfunction "1_1") (pintype "passive"))
      (node (ref "R22") (pin "2") (pinfunction "2_2") (pintype "passive"))
    )
    (net (code "30") (name "Net-(C25-Pad-)") (class "Default")
      (node (ref "C25") (pin "-") (pinfunction "-_-") (pintype "passive"))
      (node (ref "R20") (pin "2") (pinfunction "2_2") (pintype "passive"))
      (node (ref "R21") (pin "2") (pinfunction "2_2") (pintype "passive"))
    )
    (net (code "31") (name "Net-(C26-Pad1)") (class "Default")
      (node (ref "C26") (pin "1") (pinfunction "1_1") (pintype "passive"))
      (node (ref "R22") (pin "1") (pinfunction "1_1") (pintype "passive"))
    )
    (net (code "32") (name "Net-(C29-Pad+)") (class "Default")
      (node (ref "C29") (pin "+") (pinfunction "+_+") (pintype "passive"))
      (node (ref "JP4") (pin "2") (pinfunction "2_2") (pintype "passive"))
      (node (ref "R38") (pin "2") (pinfunction "2_2") (pintype "passive"))
    )
    (net (code "33") (name "Net-(C29-Pad-)") (class "Default")
      (node (ref "C29") (pin "-") (pinfunction "-_-") (pintype "passive"))
      (node (ref "R37") (pin "1") (pinfunction "1_1") (pintype "passive"))
    )
    (net (code "34") (name "Net-(C32-Pad+)") (class "Default")
      (node (ref "C32") (pin "+") (pinfunction "+_+") (pintype "passive"))
      (node (ref "R40") (pin "1") (pinfunction "1_1") (pintype "passive"))
    )
    (net (code "35") (name "Net-(C32-Pad-)") (class "Default")
      (node (ref "C32") (pin "-") (pinfunction "-_-") (pintype "passive"))
      (node (ref "R39") (pin "1") (pinfunction "1_1") (pintype "passive"))
    )
    (net (code "36") (name "Net-(C34-Pad2)") (class "Default")
      (node (ref "C34") (pin "2") (pinfunction "2_2") (pintype "passive"))
      (node (ref "R46") (pin "1") (pinfunction "1_1") (pintype "passive"))
      (node (ref "R47") (pin "2") (pinfunction "2_2") (pintype "passive"))
    )
    (net (code "37") (name "Net-(C35-Pad1)") (class "Default")
      (node (ref "C35") (pin "1") (pinfunction "1_1") (pintype "passive"))
      (node (ref "R45") (pin "1") (pinfunction "1_1") (pintype "passive"))
      (node (ref "R46") (pin "2") (pinfunction "2_2") (pintype "passive"))
    )
    (net (code "38") (name "Net-(C37-Pad2)") (class "Default")
      (node (ref "C37") (pin "2") (pinfunction "2_2") (pintype "passive"))
      (node (ref "R49") (pin "1") (pinfunction "1_1") (pintype "passive"))
      (node (ref "R50") (pin "2") (pinfunction "2_2") (pintype "passive"))
    )
    (net (code "39") (name "Net-(C38-Pad1)") (class "Default")
      (node (ref "C38") (pin "1") (pinfunction "1_1") (pintype "passive"))
      (node (ref "R48") (pin "1") (pinfunction "1_1") (pintype "passive"))
      (node (ref "R49") (pin "2") (pinfunction "2_2") (pintype "passive"))
    )
    (net (code "40") (name "Net-(D1-C1A2)") (class "Default")
      (node (ref "C8") (pin "1") (pinfunction "1_1") (pintype "passive"))
      (node (ref "D1") (pin "3") (pinfunction "C1A2_3") (pintype "passive"))
      (node (ref "R14") (pin "1") (pinfunction "1_1") (pintype "passive"))
      (node (ref "R7") (pin "1") (pinfunction "1_1") (pintype "passive"))
      (node (ref "R8") (pin "2") (pinfunction "2_2") (pintype "passive"))
    )
    (net (code "41") (name "Net-(D3-C1A2)") (class "Default")
      (node (ref "C9") (pin "1") (pinfunction "1_1") (pintype "passive"))
      (node (ref "D3") (pin "3") (pinfunction "C1A2_3") (pintype "passive"))
      (node (ref "R10") (pin "2") (pinfunction "2_2") (pintype "passive"))
      (node (ref "R15") (pin "1") (pinfunction "1_1") (pintype "passive"))
      (node (ref "R9") (pin "1") (pinfunction "1_1") (pintype "passive"))
    )
    (net (code "42") (name "Net-(D4-C1A2)") (class "Default")
      (node (ref "D4") (pin "3") (pinfunction "C1A2_3") (pintype "passive"))
      (node (ref "R31") (pin "1") (pinfunction "1_1") (pintype "passive"))
      (node (ref "R32") (pin "2") (pinfunction "2_2") (pintype "passive"))
      (node (ref "R33") (pin "1") (pinfunction "1_1") (pintype "passive"))
    )
    (net (code "43") (name "Net-(D5-C1A2)") (class "Default")
      (node (ref "D5") (pin "3") (pinfunction "C1A2_3") (pintype "passive"))
      (node (ref "R43") (pin "1") (pinfunction "1_1") (pintype "passive"))
    )
    (net (code "44") (name "Net-(D6-C1A2)") (class "Default")
      (node (ref "D6") (pin "3") (pinfunction "C1A2_3") (pintype "passive"))
      (node (ref "R41") (pin "1") (pinfunction "1_1") (pintype "passive"))
    )
    (net (code "45") (name "Net-(D7-C1A2)") (class "Default")
      (node (ref "D7") (pin "3") (pinfunction "C1A2_3") (pintype "passive"))
      (node (ref "R42") (pin "1") (pinfunction "1_1") (pintype "passive"))
    )
    (net (code "46") (name "Net-(D8-C1A2)") (class "Default")
      (node (ref "D8") (pin "3") (pinfunction "C1A2_3") (pintype "passive"))
      (node (ref "R44") (pin "1") (pinfunction "1_1") (pintype "passive"))
    )
    (net (code "47") (name "Net-(IC1A-+IN)") (class "Default")
      (node (ref "IC1") (pin "3") (pinfunction "+IN_3") (pintype "input"))
      (node (ref "R4") (pin "2") (pinfunction "2_2") (pintype "passive"))
    )
    (net (code "48") (name "Net-(IC1A--IN)") (class "Default")
      (node (ref "C10") (pin "2") (pinfunction "2_2") (pintype "passive"))
      (node (ref "IC1") (pin "2") (pinfunction "-IN_2") (pintype "input"))
      (node (ref "R1") (pin "2") (pinfunction "2_2") (pintype "passive"))
      (node (ref "R6") (pin "1") (pinfunction "1_1") (pintype "passive"))
    )
    (net (code "49") (name "Net-(IC1A-OUT)") (class "Default")
      (node (ref "C10") (pin "1") (pinfunction "1_1") (pintype "passive"))
      (node (ref "C9") (pin "2") (pinfunction "2_2") (pintype "passive"))
      (node (ref "IC1") (pin "1") (pinfunction "OUT_1") (pintype "output"))
      (node (ref "R6") (pin "2") (pinfunction "2_2") (pintype "passive"))
    )
    (net (code "50") (name "Net-(IC1B-+IN)") (class "Default")
      (node (ref "IC1") (pin "5") (pinfunction "+IN_5") (pintype "input"))
      (node (ref "R2") (pin "2") (pinfunction "2_2") (pintype "passive"))
    )
    (net (code "51") (name "Net-(IC1B--IN)") (class "Default")
      (node (ref "C7") (pin "2") (pinfunction "2_2") (pintype "passive"))
      (node (ref "IC1") (pin "6") (pinfunction "-IN_6") (pintype "input"))
      (node (ref "R3") (pin "2") (pinfunction "2_2") (pintype "passive"))
      (node (ref "R5") (pin "1") (pinfunction "1_1") (pintype "passive"))
    )
    (net (code "52") (name "Net-(IC1B-OUT)") (class "Default")
      (node (ref "C7") (pin "1") (pinfunction "1_1") (pintype "passive"))
      (node (ref "C8") (pin "2") (pinfunction "2_2") (pintype "passive"))
      (node (ref "IC1") (pin "7") (pinfunction "OUT_7") (pintype "output"))
      (node (ref "R5") (pin "2") (pinfunction "2_2") (pintype "passive"))
    )
    (net (code "53") (name "Net-(IC3A-I0)") (class "Default")
      (node (ref "IC3") (pin "1") (pinfunction "I0_1") (pintype "input"))
      (node (ref "SJ1") (pin "1") (pinfunction "1_1") (pintype "passive"))
      (node (ref "SJ4") (pin "2") (pinfunction "2_2") (pintype "passive"))
    )
    (net (code "54") (name "Net-(IC3A-I1)") (class "Default")
      (node (ref "IC3") (pin "2") (pinfunction "I1_2") (pintype "input"))
      (node (ref "SJ1") (pin "2") (pinfunction "2_2") (pintype "passive"))
      (node (ref "U$2") (pin "2") (pinfunction "2_2") (pintype "bidirectional"))
    )
    (net (code "55") (name "Net-(IC3A-O)") (class "Default")
      (node (ref "IC3") (pin "3") (pinfunction "O_3") (pintype "output"))
      (node (ref "IC3") (pin "5") (pinfunction "I1_5") (pintype "input"))
      (node (ref "SJ3") (pin "2") (pinfunction "2_2") (pintype "passive"))
    )
    (net (code "56") (name "Net-(IC3B-I0)") (class "Default")
      (node (ref "IC3") (pin "4") (pinfunction "I0_4") (pintype "input"))
      (node (ref "SJ3") (pin "1") (pinfunction "1_1") (pintype "passive"))
    )
    (net (code "57") (name "Net-(IC3B-O)") (class "Default")
      (node (ref "C20") (pin "2") (pinfunction "2_2") (pintype "passive"))
      (node (ref "IC3") (pin "6") (pinfunction "O_6") (pintype "output"))
      (node (ref "R18") (pin "1") (pinfunction "1_1") (pintype "passive"))
    )
    (net (code "58") (name "Net-(IC3C-O)") (class "Default")
      (node (ref "IC3") (pin "8") (pinfunction "O_8") (pintype "output"))
      (node (ref "U1") (pin "6") (pinfunction "1B1_6") (pintype "bidirectional"))
    )
    (net (code "59") (name "Net-(IC3D-O)") (class "Default")
      (node (ref "IC3") (pin "11") (pinfunction "O_11") (pintype "output"))
      (node (ref "U1") (pin "5") (pinfunction "1B2_5") (pintype "bidirectional"))
    )
    (net (code "60") (name "Net-(IC5-BYPASS)") (class "Default")
      (node (ref "C18") (pin "1") (pinfunction "1_1") (pintype "passive"))
      (node (ref "IC5") (pin "7") (pinfunction "BYPASS_7") (pintype "passive"))
    )
    (net (code "61") (name "Net-(IC5-GAIN-Pad8)") (class "Default")
      (node (ref "IC5") (pin "8") (pinfunction "GAIN_8") (pintype "passive"))
      (node (ref "R17") (pin "1") (pinfunction "1_1") (pintype "passive"))
      (node (ref "SJ2") (pin "1") (pinfunction "1_1") (pintype "passive"))
    )
    (net (code "62") (name "Net-(IC5-OUT)") (class "Default")
      (node (ref "C16") (pin "+") (pinfunction "+_+") (pintype "passive"))
      (node (ref "IC5") (pin "5") (pinfunction "OUT_5") (pintype "output"))
    )
    (net (code "63") (name "Net-(IC8A-+IN)") (class "Default")
      (node (ref "C30") (pin "+") (pinfunction "+_+") (pintype "passive"))
      (node (ref "IC8") (pin "3") (pinfunction "+IN_3") (pintype "input"))
      (node (ref "R35") (pin "2") (pinfunction "2_2") (pintype "passive"))
      (node (ref "R36") (pin "1") (pinfunction "1_1") (pintype "passive"))
    )
    (net (code "64") (name "Net-(IC8A--IN)") (class "Default")
      (node (ref "C31") (pin "1") (pinfunction "1_1") (pintype "passive"))
      (node (ref "IC8") (pin "2") (pinfunction "-IN_2") (pintype "input"))
      (node (ref "R34") (pin "2") (pinfunction "2_2") (pintype "passive"))
      (node (ref "R37") (pin "2") (pinfunction "2_2") (pintype "passive"))
    )
    (net (code "65") (name "Net-(IC8A-OUT)") (class "Default")
      (node (ref "C31") (pin "2") (pinfunction "2_2") (pintype "passive"))
      (node (ref "IC8") (pin "1") (pinfunction "OUT_1") (pintype "output"))
      (node (ref "R34") (pin "1") (pinfunction "1_1") (pintype "passive"))
      (node (ref "R39") (pin "2") (pinfunction "2_2") (pintype "passive"))
    )
    (net (code "66") (name "Net-(IC11A-+IN)") (class "Default")
      (node (ref "C33") (pin "2") (pinfunction "2_2") (pintype "passive"))
      (node (ref "IC11") (pin "3") (pinfunction "+IN_3") (pintype "input"))
      (node (ref "R45") (pin "2") (pinfunction "2_2") (pintype "passive"))
    )
    (net (code "67") (name "Net-(IC11A--IN)") (class "Default")
      (node (ref "C35") (pin "2") (pinfunction "2_2") (pintype "passive"))
      (node (ref "IC11") (pin "1") (pinfunction "OUT_1") (pintype "output"))
      (node (ref "IC11") (pin "2") (pinfunction "-IN_2") (pintype "input"))
      (node (ref "R50") (pin "1") (pinfunction "1_1") (pintype "passive"))
    )
    (net (code "68") (name "Net-(IC11B-+IN)") (class "Default")
      (node (ref "C36") (pin "2") (pinfunction "2_2") (pintype "passive"))
      (node (ref "IC11") (pin "5") (pinfunction "+IN_5") (pintype "input"))
      (node (ref "R48") (pin "2") (pinfunction "2_2") (pintype "passive"))
    )
    (net (code "69") (name "Net-(IC11B--IN)") (class "Default")
      (node (ref "C38") (pin "2") (pinfunction "2_2") (pintype "passive"))
      (node (ref "IC11") (pin "6") (pinfunction "-IN_6") (pintype "input"))
      (node (ref "IC11") (pin "7") (pinfunction "OUT_7") (pintype "output"))
    )
    (net (code "70") (name "Net-(R19-Pad2)") (class "Default")
      (node (ref "R19") (pin "2") (pinfunction "2_2") (pintype "passive"))
      (node (ref "U$1") (pin "VBAT") (pinfunction "VBAT_VBAT") (pintype "bidirectional"))
    )
    (net (code "71") (name "Net-(S2-S)") (class "Default")
      (node (ref "R26") (pin "1") (pinfunction "1_1") (pintype "passive"))
      (node (ref "R27") (pin "2") (pinfunction "2_2") (pintype "passive"))
      (node (ref "S2") (pin "1") (pinfunction "S_1") (pintype "passive"))
      (node (ref "S2") (pin "2") (pinfunction "S1_2") (pintype "passive"))
    )
    (net (code "72") (name "Net-(S3-S)") (class "Default")
      (node (ref "R27") (pin "1") (pinfunction "1_1") (pintype "passive"))
      (node (ref "R28") (pin "2") (pinfunction "2_2") (pintype "passive"))
      (node (ref "S3") (pin "1") (pinfunction "S_1") (pintype "passive"))
      (node (ref "S3") (pin "2") (pinfunction "S1_2") (pintype "passive"))
    )
    (net (code "73") (name "Net-(S4-S)") (class "Default")
      (node (ref "R28") (pin "1") (pinfunction "1_1") (pintype "passive"))
      (node (ref "R29") (pin "2") (pinfunction "2_2") (pintype "passive"))
      (node (ref "S4") (pin "1") (pinfunction "S_1") (pintype "passive"))
      (node (ref "S4") (pin "2") (pinfunction "S1_2") (pintype "passive"))
    )
    (net (code "74") (name "Net-(SW1B-1)") (class "Default")
      (node (ref "R29") (pin "1") (pinfunction "1_1") (pintype "passive"))
      (node (ref "R30") (pin "2") (pinfunction "2_2") (pintype "passive"))
      (node (ref "SW1") (pin "D") (pinfunction "1_D") (pintype "passive"))
    )
    (net (code "75") (name "Net-(SW2B-1)") (class "Default")
      (node (ref "R30") (pin "1") (pinfunction "1_1") (pintype "passive"))
      (node (ref "SW2") (pin "D") (pinfunction "1_D") (pintype "passive"))
    )
    (net (code "76") (name "Net-(T1-B)") (class "Default")
      (node (ref "R24") (pin "1") (pinfunction "1_1") (pintype "passive"))
      (node (ref "T1") (pin "1") (pinfunction "B_1") (pintype "passive"))
    )
    (net (code "77") (name "Net-(U1-1A)") (class "Default")
      (node (ref "SJ4") (pin "1") (pinfunction "1_1") (pintype "passive"))
      (node (ref "U1") (pin "7") (pinfunction "1A_7") (pintype "bidirectional"))
    )
    (net (code "78") (name "Net-(U1-2A)") (class "Default")
      (node (ref "C11") (pin "2") (pinfunction "2_2") (pintype "passive"))
      (node (ref "R11") (pin "2") (pinfunction "2_2") (pintype "passive"))
      (node (ref "U1") (pin "9") (pinfunction "2A_9") (pintype "bidirectional"))
    )
    (net (code "79") (name "Net-(U1-2B1)") (class "Default")
      (node (ref "C3") (pin "1") (pinfunction "1_1") (pintype "passive"))
      (node (ref "R1") (pin "1") (pinfunction "1_1") (pintype "passive"))
      (node (ref "U1") (pin "10") (pinfunction "2B1_10") (pintype "bidirectional"))
    )
    (net (code "80") (name "Net-(U1-2B2)") (class "Default")
      (node (ref "C4") (pin "1") (pinfunction "1_1") (pintype "passive"))
      (node (ref "R2") (pin "1") (pinfunction "1_1") (pintype "passive"))
      (node (ref "U1") (pin "11") (pinfunction "2B2_11") (pintype "bidirectional"))
    )
    (net (code "81") (name "Net-(U1-2B3)") (class "Default")
      (node (ref "C5") (pin "2") (pinfunction "2_2") (pintype "passive"))
      (node (ref "R3") (pin "1") (pinfunction "1_1") (pintype "passive"))
      (node (ref "U1") (pin "12") (pinfunction "2B3_12") (pintype "bidirectional"))
    )
    (net (code "82") (name "Net-(U1-2B4)") (class "Default")
      (node (ref "C6") (pin "2") (pinfunction "2_2") (pintype "passive"))
      (node (ref "R4") (pin "1") (pinfunction "1_1") (pintype "passive"))
      (node (ref "U1") (pin "13") (pinfunction "2B4_13") (pintype "bidirectional"))
    )
    (net (code "83") (name "Net-(U1-S0)") (class "Default")
      (node (ref "U$2") (pin "0") (pinfunction "0_0") (pintype "bidirectional"))
      (node (ref "U1") (pin "14") (pinfunction "S0_14") (pintype "bidirectional"))
    )
    (net (code "84") (name "Net-(U1-S1)") (class "Default")
      (node (ref "U$2") (pin "1") (pinfunction "1_1") (pintype "bidirectional"))
      (node (ref "U1") (pin "2") (pinfunction "S1_2") (pintype "bidirectional"))
    )
    (net (code "86") (name "RESET") (class "Default")
      (node (ref "U$1") (pin "RESET") (pinfunction "RESET_RESET") (pintype "bidirectional"))
    )
    (net (code "87") (name "RTC_OSC_IN") (class "Default")
      (node (ref "U$1") (pin "C14") (pinfunction "PC14_C14") (pintype "bidirectional"))
    )
    (net (code "88") (name "RTC_OSC_OUT") (class "Default")
      (node (ref "U$1") (pin "C15") (pinfunction "PC15_C15") (pintype "bidirectional"))
    )
    (net (code "89") (name "RX") (class "Default")
      (node (ref "C11") (pin "1") (pinfunction "1_1") (pintype "passive"))
    )
    (net (code "90") (name "RXEN") (class "Default")
      (node (ref "IC7") (pin "13") (pinfunction "C_13") (pintype "input"))
      (node (ref "IC7") (pin "5") (pinfunction "C_5") (pintype "input"))
      (node (ref "R23") (pin "1") (pinfunction "1_1") (pintype "passive"))
      (node (ref "T1") (pin "3") (pinfunction "C_3") (pintype "passive"))
    )
    (net (code "91") (name "RX_I") (class "Default")
      (node (ref "IC7") (pin "1") (pinfunction "A_1") (pintype "tri_state"))
      (node (ref "R14") (pin "2") (pinfunction "2_2") (pintype "passive"))
    )
    (net (code "92") (name "RX_Q") (class "Default")
      (node (ref "IC7") (pin "4") (pinfunction "A_4") (pintype "tri_state"))
      (node (ref "R15") (pin "2") (pinfunction "2_2") (pintype "passive"))
    )
    (net (code "93") (name "SCL") (class "Default")
      (node (ref "U$1") (pin "B10") (pinfunction "PB10_B10") (pintype "bidirectional"))
      (node (ref "U$2") (pin "SCL") (pinfunction "SCL_SCL") (pintype "bidirectional"))
    )
    (net (code "94") (name "SDA") (class "Default")
      (node (ref "U$1") (pin "B11") (pinfunction "PB11_B11") (pintype "bidirectional"))
      (node (ref "U$2") (pin "SDA") (pinfunction "SDA_SDA") (pintype "bidirectional"))
    )
    (net (code "95") (name "SPI_MISO") (class "Default")
      (node (ref "U$1") (pin "B4") (pinfunction "PB4_B4") (pintype "bidirectional"))
    )
    (net (code "96") (name "SPI_MOSI") (class "Default")
      (node (ref "IC12") (pin "14") (pinfunction "SER_14") (pintype "input"))
      (node (ref "U$1") (pin "B5") (pinfunction "PB5_B5") (pintype "bidirectional"))
      (node (ref "U$4") (pin "SDA") (pinfunction "SDA_SDA") (pintype "bidirectional"))
    )
    (net (code "97") (name "SPI_SCK") (class "Default")
      (node (ref "IC12") (pin "11") (pinfunction "SCK_11") (pintype "input"))
      (node (ref "U$1") (pin "B3") (pinfunction "PB3_B3") (pintype "bidirectional"))
      (node (ref "U$4") (pin "SCK") (pinfunction "SCK_SCK") (pintype "bidirectional"))
    )
    (net (code "98") (name "TX") (class "Default")
      (node (ref "C20") (pin "1") (pinfunction "1_1") (pintype "passive"))
      (node (ref "R18") (pin "2") (pinfunction "2_2") (pintype "passive"))
    )
    (net (code "99") (name "TXEN") (class "Default")
      (node (ref "IC7") (pin "12") (pinfunction "C_12") (pintype "input"))
      (node (ref "IC7") (pin "6") (pinfunction "C_6") (pintype "input"))
      (node (ref "R24") (pin "2") (pinfunction "2_2") (pintype "passive"))
    )
    (net (code "100") (name "TX_I") (class "Default")
      (node (ref "IC3") (pin "12") (pinfunction "I0_12") (pintype "input"))
      (node (ref "IC3") (pin "13") (pinfunction "I1_13") (pintype "input"))
      (node (ref "U1") (pin "3") (pinfunction "1B4_3") (pintype "bidirectional"))
    )
    (net (code "101") (name "TX_I_PWM") (class "Default")
      (node (ref "U$1") (pin "A8") (pinfunction "PA8_A8") (pintype "bidirectional"))
    )
    (net (code "102") (name "TX_Q") (class "Default")
      (node (ref "IC3") (pin "10") (pinfunction "I1_10") (pintype "input"))
      (node (ref "IC3") (pin "9") (pinfunction "I0_9") (pintype "input"))
      (node (ref "U1") (pin "4") (pinfunction "1B3_4") (pintype "bidirectional"))
    )
    (net (code "103") (name "TX_Q_PWM") (class "Default")
      (node (ref "U$1") (pin "A11") (pinfunction "PA11_A11") (pintype "bidirectional"))
    )
    (net (code "104") (name "UART_RX") (class "Default")
      (node (ref "U$1") (pin "B7") (pinfunction "PB7_B7") (pintype "bidirectional"))
    )
    (net (code "105") (name "UART_TX") (class "Default")
      (node (ref "U$1") (pin "B6") (pinfunction "PB6_B6") (pintype "bidirectional"))
    )
    (net (code "106") (name "V+") (class "Default")
      (node (ref "IC11") (pin "8") (pinfunction "V+_8") (pintype "power_in"))
    )
    (net (code "107") (name "V-") (class "Default")
      (node (ref "IC11") (pin "4") (pinfunction "V-_4") (pintype "power_in"))
    )
    (net (code "108") (name "VBAT") (class "Default")
      (node (ref "R31") (pin "2") (pinfunction "2_2") (pintype "passive"))
    )
    (net (code "109") (name "VDD") (class "Default")
      (node (ref "IC7") (pin "14") (pinfunction "VDD_14") (pintype "power_in"))
    )
    (net (code "110") (name "VIN") (class "Default")
      (node (ref "C21") (pin "2") (pinfunction "2_2") (pintype "passive"))
      (node (ref "IC2") (pin "1") (pinfunction "VI_1") (pintype "input"))
      (node (ref "U$3") (pin "IN-.1") (pinfunction "IN-.1_IN-.1") (pintype "bidirectional"))
      (node (ref "U$3") (pin "IN-.2") (pinfunction "IN-.2_IN-.2") (pintype "bidirectional"))
    )
    (net (code "111") (name "VOPAMP") (class "Default")
      (node (ref "C14") (pin "2") (pinfunction "2_2") (pintype "passive"))
      (node (ref "C28") (pin "2") (pinfunction "2_2") (pintype "passive"))
      (node (ref "IC1") (pin "8") (pinfunction "V+_8") (pintype "power_in"))
      (node (ref "IC8") (pin "8") (pinfunction "V+_8") (pintype "power_in"))
      (node (ref "R35") (pin "1") (pinfunction "1_1") (pintype "passive"))
      (node (ref "R38") (pin "1") (pinfunction "1_1") (pintype "passive"))
    )
    (net (code "112") (name "VSS") (class "Default")
      (node (ref "IC7") (pin "7") (pinfunction "VSS_7") (pintype "power_in"))
    )
    (net (code "113") (name "unconnected-(C25-Pad+)") (class "Default")
      (node (ref "C25") (pin "+") (pinfunction "+_+") (pintype "passive"))
    )
    (net (code "114") (name "unconnected-(D2-A1-Pad1)") (class "Default")
      (node (ref "D2") (pin "1") (pinfunction "A1_1") (pintype "passive"))
    )
    (net (code "115") (name "unconnected-(D2-C1A2-Pad3)") (class "Default")
      (node (ref "D2") (pin "3") (pinfunction "C1A2_3") (pintype "passive"))
    )
    (net (code "116") (name "unconnected-(D2-C2-Pad2)") (class "Default")
      (node (ref "D2") (pin "2") (pinfunction "C2_2") (pintype "passive"))
    )
    (net (code "117") (name "unconnected-(IC8B-+IN-Pad5)") (class "Default")
      (node (ref "IC8") (pin "5") (pinfunction "+IN_5") (pintype "input"))
    )
    (net (code "118") (name "unconnected-(IC8B--IN-Pad6)") (class "Default")
      (node (ref "IC8") (pin "6") (pinfunction "-IN_6") (pintype "input"))
    )
    (net (code "119") (name "unconnected-(IC8B-OUT-Pad7)") (class "Default")
      (node (ref "IC8") (pin "7") (pinfunction "OUT_7") (pintype "output"))
    )
    (net (code "120") (name "unconnected-(IC9-GND-Pad2)") (class "Default")
      (node (ref "IC9") (pin "2") (pinfunction "GND_2") (pintype "passive"))
    )
    (net (code "121") (name "unconnected-(IC9-VI-Pad3)") (class "Default")
      (node (ref "IC9") (pin "3") (pinfunction "VI_3") (pintype "input"))
    )
    (net (code "122") (name "unconnected-(IC9-VO-Pad1)") (class "Default")
      (node (ref "IC9") (pin "1") (pinfunction "VO_1") (pintype "passive"))
    )
    (net (code "123") (name "unconnected-(IC10-GND-Pad2)") (class "Default")
      (node (ref "IC10") (pin "2") (pinfunction "GND_2") (pintype "passive"))
    )
    (net (code "124") (name "unconnected-(IC10-VI-Pad3)") (class "Default")
      (node (ref "IC10") (pin "3") (pinfunction "VI_3") (pintype "input"))
    )
    (net (code "125") (name "unconnected-(IC10-VO-Pad1)") (class "Default")
      (node (ref "IC10") (pin "1") (pinfunction "VO_1") (pintype "passive"))
    )
    (net (code "126") (name "unconnected-(IC12A-QA-Pad15)") (class "Default")
      (node (ref "IC12") (pin "15") (pinfunction "QA_15") (pintype "tri_state"))
    )
    (net (code "127") (name "unconnected-(IC12A-QB-Pad1)") (class "Default")
      (node (ref "IC12") (pin "1") (pinfunction "QB_1") (pintype "tri_state"))
    )
    (net (code "128") (name "unconnected-(IC12A-QC-Pad2)") (class "Default")
      (node (ref "IC12") (pin "2") (pinfunction "QC_2") (pintype "tri_state"))
    )
    (net (code "129") (name "unconnected-(IC12A-QD-Pad3)") (class "Default")
      (node (ref "IC12") (pin "3") (pinfunction "QD_3") (pintype "tri_state"))
    )
    (net (code "130") (name "unconnected-(IC12A-QE-Pad4)") (class "Default")
      (node (ref "IC12") (pin "4") (pinfunction "QE_4") (pintype "tri_state"))
    )
    (net (code "131") (name "unconnected-(IC12A-QF-Pad5)") (class "Default")
      (node (ref "IC12") (pin "5") (pinfunction "QF_5") (pintype "tri_state"))
    )
    (net (code "132") (name "unconnected-(IC12A-QG-Pad6)") (class "Default")
      (node (ref "IC12") (pin "6") (pinfunction "QG_6") (pintype "tri_state"))
    )
    (net (code "133") (name "unconnected-(IC12A-QH*-Pad9)") (class "Default")
      (node (ref "IC12") (pin "9") (pinfunction "QH*_9") (pintype "tri_state"))
    )
    (net (code "134") (name "unconnected-(IC12A-QH-Pad7)") (class "Default")
      (node (ref "IC12") (pin "7") (pinfunction "QH_7") (pintype "tri_state"))
    )
    (net (code "135") (name "unconnected-(IC12A-SCL-Pad10)") (class "Default")
      (node (ref "IC12") (pin "10") (pinfunction "SCL_10") (pintype "input"))
    )
    (net (code "136") (name "unconnected-(J1-Pad1)") (class "Default")
      (node (ref "J1") (pin "1") (pinfunction "1_1") (pintype "passive"))
    )
    (net (code "137") (name "unconnected-(J1-Pad2)") (class "Default")
      (node (ref "J1") (pin "2") (pinfunction "2_2") (pintype "passive"))
    )
    (net (code "138") (name "unconnected-(J1-Pad3)") (class "Default")
      (node (ref "J1") (pin "3") (pinfunction "3_3") (pintype "passive"))
    )
    (net (code "139") (name "unconnected-(J1-Pad4)") (class "Default")
      (node (ref "J1") (pin "4") (pinfunction "4_4") (pintype "passive"))
    )
    (net (code "140") (name "unconnected-(J1-Pad5)") (class "Default")
      (node (ref "J1") (pin "5") (pinfunction "5_5") (pintype "passive"))
    )
    (net (code "141") (name "unconnected-(J2-Pad1)") (class "Default")
      (node (ref "J2") (pin "1") (pinfunction "1_1") (pintype "passive"))
    )
    (net (code "142") (name "unconnected-(J2-Pad2)") (class "Default")
      (node (ref "J2") (pin "2") (pinfunction "2_2") (pintype "passive"))
    )
    (net (code "143") (name "unconnected-(J2-Pad3)") (class "Default")
      (node (ref "J2") (pin "3") (pinfunction "3_3") (pintype "passive"))
    )
    (net (code "144") (name "unconnected-(J2-Pad4)") (class "Default")
      (node (ref "J2") (pin "4") (pinfunction "4_4") (pintype "passive"))
    )
    (net (code "145") (name "unconnected-(J2-Pad5)") (class "Default")
      (node (ref "J2") (pin "5") (pinfunction "5_5") (pintype "passive"))
    )
    (net (code "146") (name "unconnected-(J3-Pad1)") (class "Default")
      (node (ref "J3") (pin "1") (pinfunction "1_1") (pintype "passive"))
    )
    (net (code "147") (name "unconnected-(J3-Pad2)") (class "Default")
      (node (ref "J3") (pin "2") (pinfunction "2_2") (pintype "passive"))
    )
    (net (code "148") (name "unconnected-(J3-Pad3)") (class "Default")
      (node (ref "J3") (pin "3") (pinfunction "3_3") (pintype "passive"))
    )
    (net (code "149") (name "unconnected-(J3-Pad4)") (class "Default")
      (node (ref "J3") (pin "4") (pinfunction "4_4") (pintype "passive"))
    )
    (net (code "150") (name "unconnected-(J3-Pad5)") (class "Default")
      (node (ref "J3") (pin "5") (pinfunction "5_5") (pintype "passive"))
    )
    (net (code "151") (name "unconnected-(JP1-Pad1)") (class "Default")
      (node (ref "JP1") (pin "1") (pinfunction "1_1") (pintype "passive"))
    )
    (net (code "152") (name "unconnected-(JP2-Pad1)") (class "Default")
      (node (ref "JP2") (pin "1") (pinfunction "1_1") (pintype "passive"))
    )
    (net (code "153") (name "unconnected-(LED1-PadA)") (class "Default")
      (node (ref "LED1") (pin "A") (pinfunction "A_A") (pintype "passive"))
    )
    (net (code "154") (name "unconnected-(LED1-PadC)") (class "Default")
      (node (ref "LED1") (pin "C") (pinfunction "C_C") (pintype "passive"))
    )
    (net (code "155") (name "unconnected-(LED2-PadA)") (class "Default")
      (node (ref "LED2") (pin "A") (pinfunction "A_A") (pintype "passive"))
    )
    (net (code "156") (name "unconnected-(LED2-PadC)") (class "Default")
      (node (ref "LED2") (pin "C") (pinfunction "C_C") (pintype "passive"))
    )
    (net (code "157") (name "unconnected-(LED3-PadA)") (class "Default")
      (node (ref "LED3") (pin "A") (pinfunction "A_A") (pintype "passive"))
    )
    (net (code "158") (name "unconnected-(LED3-PadC)") (class "Default")
      (node (ref "LED3") (pin "C") (pinfunction "C_C") (pintype "passive"))
    )
    (net (code "159") (name "unconnected-(R41-Pad2)") (class "Default")
      (node (ref "R41") (pin "2") (pinfunction "2_2") (pintype "passive"))
    )
    (net (code "160") (name "unconnected-(R42-Pad2)") (class "Default")
      (node (ref "R42") (pin "2") (pinfunction "2_2") (pintype "passive"))
    )
    (net (code "161") (name "unconnected-(R43-Pad2)") (class "Default")
      (node (ref "R43") (pin "2") (pinfunction "2_2") (pintype "passive"))
    )
    (net (code "162") (name "unconnected-(R44-Pad2)") (class "Default")
      (node (ref "R44") (pin "2") (pinfunction "2_2") (pintype "passive"))
    )
    (net (code "163") (name "unconnected-(R47-Pad1)") (class "Default")
      (node (ref "R47") (pin "1") (pinfunction "1_1") (pintype "passive"))
    )
    (net (code "164") (name "unconnected-(SW1-PadA)") (class "Default")
      (node (ref "SW1") (pin "A") (pinfunction "A_A") (pintype "passive"))
    )
    (net (code "165") (name "unconnected-(SW1-PadB)") (class "Default")
      (node (ref "SW1") (pin "B") (pinfunction "B_B") (pintype "passive"))
    )
    (net (code "166") (name "unconnected-(SW2-PadA)") (class "Default")
      (node (ref "SW2") (pin "A") (pinfunction "A_A") (pintype "passive"))
    )
    (net (code "167") (name "unconnected-(SW2-PadB)") (class "Default")
      (node (ref "SW2") (pin "B") (pinfunction "B_B") (pintype "passive"))
    )
    (net (code "168") (name "unconnected-(U$1-3.3V1-Pad3V31)") (class "Default")
      (node (ref "U$1") (pin "3V31") (pinfunction "3.3V1_3V31") (pintype "bidirectional"))
    )
    (net (code "169") (name "unconnected-(U$1-PA7-PadA7)") (class "Default")
      (node (ref "U$1") (pin "A7") (pinfunction "PA7_A7") (pintype "bidirectional"))
    )
    (net (code "170") (name "unconnected-(U$1-PB0-PadB0)") (class "Default")
      (node (ref "U$1") (pin "B0") (pinfunction "PB0_B0") (pintype "bidirectional"))
    )
    (net (code "171") (name "unconnected-(U$1-PB1-PadB1)") (class "Default")
      (node (ref "U$1") (pin "B1") (pinfunction "PB1_B1") (pintype "bidirectional"))
    )
    (net (code "172") (name "unconnected-(U$1-PB8-PadB8)") (class "Default")
      (node (ref "U$1") (pin "B8") (pinfunction "PB8_B8") (pintype "bidirectional"))
    )
    (net (code "173") (name "unconnected-(U$1-PB9-PadB9)") (class "Default")
      (node (ref "U$1") (pin "B9") (pinfunction "PB9_B9") (pintype "bidirectional"))
    )
    (net (code "174") (name "unconnected-(U$1-PB12-PadB12)") (class "Default")
      (node (ref "U$1") (pin "B12") (pinfunction "PB12_B12") (pintype "bidirectional"))
    )
    (net (code "175") (name "unconnected-(U$1-PB13-PadB13)") (class "Default")
      (node (ref "U$1") (pin "B13") (pinfunction "PB13_B13") (pintype "bidirectional"))
    )
    (net (code "176") (name "unconnected-(U$1-PB14-PadB14)") (class "Default")
      (node (ref "U$1") (pin "B14") (pinfunction "PB14_B14") (pintype "bidirectional"))
    )
    (net (code "177") (name "unconnected-(U$1-PB15-PadB15)") (class "Default")
      (node (ref "U$1") (pin "B15") (pinfunction "PB15_B15") (pintype "bidirectional"))
    )
    (net (code "178") (name "unconnected-(U$1-Pad5V)") (class "Default")
      (node (ref "U$1") (pin "5V") (pinfunction "5V_5V") (pintype "bidirectional"))
    )
    (net (code "179") (name "unconnected-(U$1-PadGND2)") (class "Default")
      (node (ref "U$1") (pin "GND2") (pinfunction "GND2_GND2") (pintype "bidirectional"))
    )
  )
)
